# PowerSuppy.net
KiCad netlist of a schematic drawn in Altium Designer
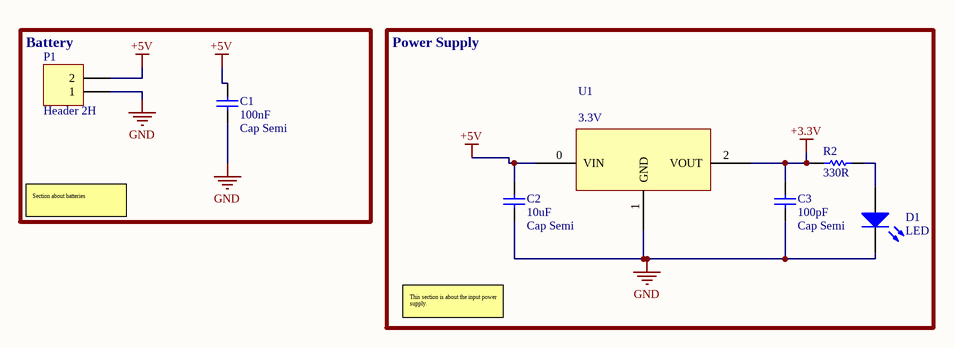
[diagram p0: PowerSuppy.SchDoc]

(export (version "E")
  (design (tool "Eeschema 10.0.6"))
  (components
    (comp (ref "C1")
      (value "Cap Semi")
      (footprint "C1206")
      (description "Capacitor (Semiconductor SIM Model)")
      (fields (field (name "ALTIUM_VALUE") "100nF") (field (name "PUBLISHER") "Altium Limited"))
      (libsource (lib "Miscellaneous Devices") (part "Cap Semi"))
    )
    (comp (ref "C2")
      (value "Cap Semi")
      (footprint "C1206")
      (description "Capacitor (Semiconductor SIM Model)")
      (fields (field (name "ALTIUM_VALUE") "10uF") (field (name "PUBLISHER") "Altium Limited"))
      (libsource (lib "Miscellaneous Devices") (part "Cap Semi"))
    )
    (comp (ref "C3")
      (value "Cap Semi")
      (footprint "C1206")
      (description "Capacitor (Semiconductor SIM Model)")
      (fields (field (name "ALTIUM_VALUE") "100pF") (field (name "PUBLISHER") "Altium Limited"))
      (libsource (lib "Miscellaneous Devices") (part "Cap Semi"))
    )
    (comp (ref "D1")
      (value "LED")
      (footprint "MY_LED_0805")
      (description "Typical INFRARED GaAs LED")
      (fields (field (name "ASID PART NUMBER") "LED-AS"))
      (libsource (lib "Mylib+Rev+4") (part "LED"))
    )
    (comp (ref "P1")
      (value "Header 2H")
      (footprint "HDR1X2H")
      (description "Header, 2-Pin, Right Angle")
      (fields (field (name "PUBLISHER") "Altium Limited"))
      (libsource (lib "Miscellaneous Connectors") (part "Header 2H"))
    )
    (comp (ref "R2")
      (value "330R")
      (footprint "MY_0805")
      (description "Standard resistor")
      (fields (field (name "ASID PART NUMBER") "Res-AS"))
      (libsource (lib "Mylib+Rev+4") (part "Res"))
    )
    (comp (ref "U1")
      (value "~")
      (footprint "4-Pin SOT")
      (fields (field (name "OUTPUT VOLTAGE") "3.3V"))
      (libsource (lib "smartmcu(IntegratedLib)") (part "lm1117"))
    )
  )
  (nets
    (net (code "1") (name "+3.3V") (class "Default")
      (node (ref "C3") (pin "2") (pinfunction "2_2") (pintype "passive"))
      (node (ref "R2") (pin "1") (pinfunction "1_1") (pintype "passive"))
      (node (ref "U1") (pin "2") (pinfunction "VOUT_2") (pintype "passive"))
    )
    (net (code "2") (name "+5V") (class "Default")
      (node (ref "C1") (pin "2") (pinfunction "2_2") (pintype "passive"))
      (node (ref "C2") (pin "2") (pinfunction "2_2") (pintype "passive"))
      (node (ref "P1") (pin "2") (pinfunction "2_2") (pintype "passive"))
      (node (ref "U1") (pin "0") (pinfunction "VIN_0") (pintype "passive"))
    )
    (net (code "3") (name "GND") (class "Default")
      (node (ref "C1") (pin "1") (pinfunction "1_1") (pintype "passive"))
      (node (ref "C2") (pin "1") (pinfunction "1_1") (pintype "passive"))
      (node (ref "C3") (pin "1") (pinfunction "1_1") (pintype "passive"))
      (node (ref "D1") (pin "K") (pinfunction "K_K") (pintype "passive"))
      (node (ref "P1") (pin "1") (pinfunction "1_1") (pintype "passive"))
      (node (ref "U1") (pin "1") (pinfunction "GND_1") (pintype "passive"))
    )
    (net (code "4") (name "Net-(D1-PadA)") (class "Default")
      (node (ref "D1") (pin "A") (pinfunction "A_A") (pintype "passive"))
      (node (ref "R2") (pin "2") (pinfunction "2_2") (pintype "passive"))
    )
  )
)
